# SCH-6-ESC4.net
KiCad netlist of a schematic drawn in Altium Designer
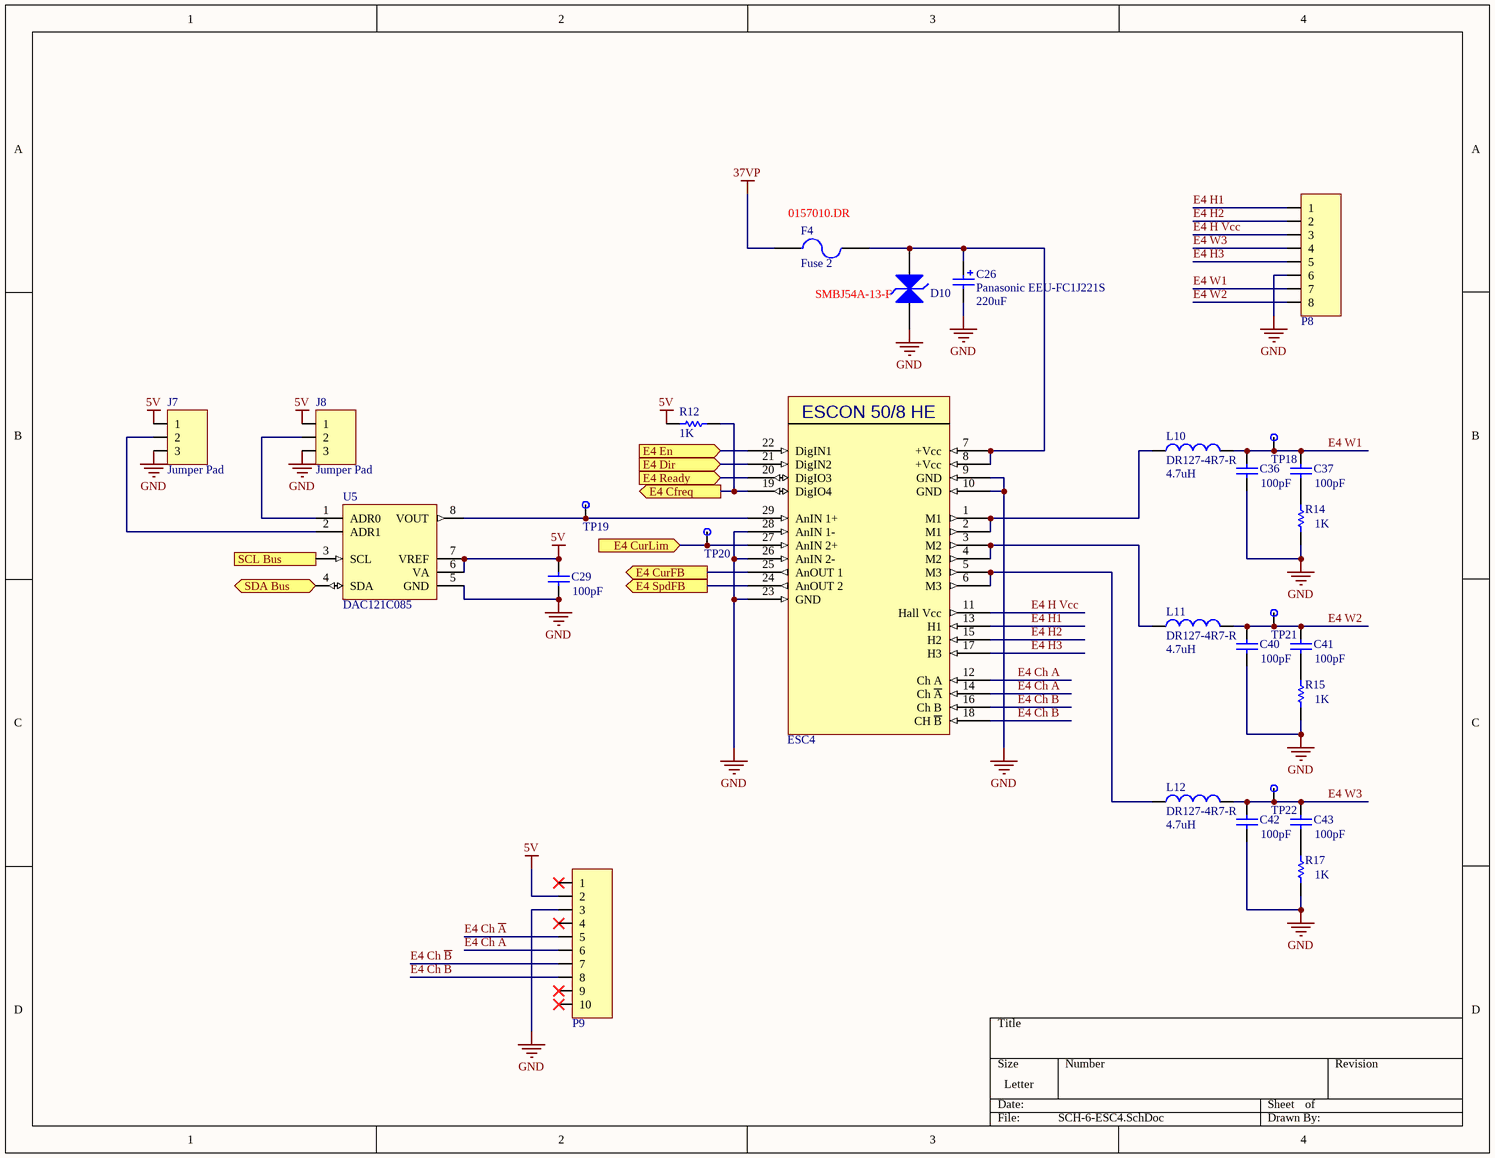
[diagram p0: SCH-6-ESC4.SchDoc]

(export (version "E")
  (design (tool "Eeschema 10.0.6"))
  (components
    (comp (ref "C26")
      (value "Panasonic EEU-FC1J221S")
      (footprint "Panasonic EEU-FC1J221S")
      (description "Polarized Capacitor (Radial)")
      (fields (field (name "ALTIUM_VALUE") "220uF"))
      (libsource (lib "RSX_Capacitors") (part "Panasonic EEU-FC1J221S"))
    )
    (comp (ref "C29")
      (value "100pF")
      (footprint "C1206")
      (description "Capacitor (Semiconductor SIM Model)")
      (fields (field (name "Comment") "Cap Semi") (field (name "PUBLISHER") "Altium Limited"))
      (libsource (lib "Miscellaneous Devices") (part "Cap Semi"))
    )
    (comp (ref "C36")
      (value "100pF")
      (footprint "C1206")
      (description "Capacitor (Semiconductor SIM Model)")
      (fields (field (name "Comment") "Cap Semi") (field (name "PUBLISHER") "Altium Limited"))
      (libsource (lib "Miscellaneous Devices") (part "Cap Semi"))
    )
    (comp (ref "C37")
      (value "100pF")
      (footprint "C1206")
      (description "Capacitor (Semiconductor SIM Model)")
      (fields (field (name "Comment") "Cap Semi") (field (name "PUBLISHER") "Altium Limited"))
      (libsource (lib "Miscellaneous Devices") (part "Cap Semi"))
    )
    (comp (ref "C40")
      (value "100pF")
      (footprint "C1206")
      (description "Capacitor (Semiconductor SIM Model)")
      (fields (field (name "Comment") "Cap Semi") (field (name "PUBLISHER") "Altium Limited"))
      (libsource (lib "Miscellaneous Devices") (part "Cap Semi"))
    )
    (comp (ref "C41")
      (value "100pF")
      (footprint "C1206")
      (description "Capacitor (Semiconductor SIM Model)")
      (fields (field (name "Comment") "Cap Semi") (field (name "PUBLISHER") "Altium Limited"))
      (libsource (lib "Miscellaneous Devices") (part "Cap Semi"))
    )
    (comp (ref "C42")
      (value "100pF")
      (footprint "C1206")
      (description "Capacitor (Semiconductor SIM Model)")
      (fields (field (name "Comment") "Cap Semi") (field (name "PUBLISHER") "Altium Limited"))
      (libsource (lib "Miscellaneous Devices") (part "Cap Semi"))
    )
    (comp (ref "C43")
      (value "100pF")
      (footprint "C1206")
      (description "Capacitor (Semiconductor SIM Model)")
      (fields (field (name "Comment") "Cap Semi") (field (name "PUBLISHER") "Altium Limited"))
      (libsource (lib "Miscellaneous Devices") (part "Cap Semi"))
    )
    (comp (ref "D10")
      (value "TVS_DIODE")
      (footprint "SMBJ54A-13-F")
      (description "TVS Diode")
      (fields (field (name "PUBLISHER") "Altium Limited"))
      (libsource (lib "RSX_Diodes") (part "TVS_DIODE"))
    )
    (comp (ref "ESC4")
      (value "ESCON 50/8 HE")
      (footprint "ESCON 50/8 HE")
      (description "ESCON Module 50/8 HE Servocontroller")
      (libsource (lib "RSX_Modules") (part "ESCON 50/8 HE"))
    )
    (comp (ref "F4")
      (value "Fuse 2")
      (footprint "0157010.DR")
      (description "Fuse")
      (fields (field (name "PUBLISHER") "Altium Limited"))
      (libsource (lib "RSX_Miscellaneous") (part "Fuse 2"))
    )
    (comp (ref "J7")
      (value "Jumper Pad")
      (footprint "3 Pad TH")
      (libsource (lib "RSX_Test_Points") (part "3 Pad Jump Sel"))
    )
    (comp (ref "J8")
      (value "Jumper Pad")
      (footprint "3 Pad TH")
      (libsource (lib "RSX_Test_Points") (part "3 Pad Jump Sel"))
    )
    (comp (ref "L10")
      (value "DR127-4R7-R")
      (footprint "DR127-4R7-R")
      (description "4.7µH Shielded Wirewound Inductor 8.25A 9.17mOhm Nonstandard")
      (fields (field (name "ALTIUM_VALUE") "4.7uH") (field (name "PUBLISHER") "Altium Limited"))
      (libsource (lib "RSX_Inductors") (part "DR127-4R7-R"))
    )
    (comp (ref "L11")
      (value "DR127-4R7-R")
      (footprint "DR127-4R7-R")
      (description "4.7µH Shielded Wirewound Inductor 8.25A 9.17mOhm Nonstandard")
      (fields (field (name "ALTIUM_VALUE") "4.7uH") (field (name "PUBLISHER") "Altium Limited"))
      (libsource (lib "RSX_Inductors") (part "DR127-4R7-R"))
    )
    (comp (ref "L12")
      (value "DR127-4R7-R")
      (footprint "DR127-4R7-R")
      (description "4.7µH Shielded Wirewound Inductor 8.25A 9.17mOhm Nonstandard")
      (fields (field (name "ALTIUM_VALUE") "4.7uH") (field (name "PUBLISHER") "Altium Limited"))
      (libsource (lib "RSX_Inductors") (part "DR127-4R7-R"))
    )
    (comp (ref "P8")
      (value "Mini-Fit Jr 8 Pos")
      (footprint "Molex Mini-Fit Jr 0039281083")
      (libsource (lib "RSX_Connectors") (part "Molex Mini-Fit Jr 8pos Vert"))
    )
    (comp (ref "P9")
      (value "Header_10_Pos_Ribbon Male")
      (footprint "3M_2510-6002UB")
      (description "3M_2510-6002UB")
      (libsource (lib "RSX_Connectors") (part "Header_10_Pos_Ribbon Male"))
    )
    (comp (ref "R12")
      (value "1K")
      (footprint "RESC1608X06N_0603")
      (description "Resistor")
      (fields (field (name "Comment") "Res1") (field (name "PUBLISHER") "Altium Limited"))
      (libsource (lib "RSX_Resistors") (part "Res1"))
    )
    (comp (ref "R14")
      (value "1K")
      (footprint "RESC1608X06N_0603")
      (description "Resistor")
      (fields (field (name "Comment") "Res1") (field (name "PUBLISHER") "Altium Limited"))
      (libsource (lib "RSX_Resistors") (part "Res1"))
    )
    (comp (ref "R15")
      (value "1K")
      (footprint "RESC1608X06N_0603")
      (description "Resistor")
      (fields (field (name "Comment") "Res1") (field (name "PUBLISHER") "Altium Limited"))
      (libsource (lib "RSX_Resistors") (part "Res1"))
    )
    (comp (ref "R17")
      (value "1K")
      (footprint "RESC1608X06N_0603")
      (description "Resistor")
      (fields (field (name "Comment") "Res1") (field (name "PUBLISHER") "Altium Limited"))
      (libsource (lib "RSX_Resistors") (part "Res1"))
    )
    (comp (ref "TP18")
      (value "TestPt")
      (footprint "50_MIL_PAD")
      (libsource (lib "RSX_Test_Points") (part "TestPt"))
    )
    (comp (ref "TP19")
      (value "TestPt")
      (footprint "50_MIL_PAD")
      (libsource (lib "RSX_Test_Points") (part "TestPt"))
    )
    (comp (ref "TP20")
      (value "TestPt")
      (footprint "50_MIL_PAD")
      (libsource (lib "RSX_Test_Points") (part "TestPt"))
    )
    (comp (ref "TP21")
      (value "TestPt")
      (footprint "50_MIL_PAD")
      (libsource (lib "RSX_Test_Points") (part "TestPt"))
    )
    (comp (ref "TP22")
      (value "TestPt")
      (footprint "50_MIL_PAD")
      (libsource (lib "RSX_Test_Points") (part "TestPt"))
    )
    (comp (ref "U5")
      (value "DAC121C085")
      (footprint "MUA08A_L")
      (fields (field (name "MANUFACTURER") "National Semiconductor"))
      (libsource (lib "RSX_Schematics") (part "DAC121C085"))
    )
  )
  (nets
    (net (code "1") (name "/E4 Cfreq") (class "Default")
      (node (ref "ESC4") (pin "19") (pinfunction "DigIO4_19") (pintype "bidirectional"))
      (node (ref "R12") (pin "1") (pinfunction "1_1") (pintype "passive"))
    )
    (net (code "2") (name "/E4 Ch A") (class "Default")
      (node (ref "ESC4") (pin "12") (pinfunction "Ch_A_12") (pintype "input"))
      (node (ref "P9") (pin "6") (pinfunction "6_6") (pintype "passive"))
    )
    (net (code "3") (name "/E4 Ch B") (class "Default")
      (node (ref "ESC4") (pin "16") (pinfunction "Ch_B_16") (pintype "input"))
      (node (ref "P9") (pin "8") (pinfunction "8_8") (pintype "passive"))
    )
    (net (code "4") (name "/E4 Ch ~{A}") (class "Default")
      (node (ref "ESC4") (pin "14") (pinfunction "Ch_~{A}_14") (pintype "input"))
      (node (ref "P9") (pin "5") (pinfunction "5_5") (pintype "passive"))
    )
    (net (code "5") (name "/E4 Ch ~{B}") (class "Default")
      (node (ref "ESC4") (pin "18") (pinfunction "CH_~{B}_18") (pintype "input"))
      (node (ref "P9") (pin "7") (pinfunction "7_7") (pintype "passive"))
    )
    (net (code "6") (name "/E4 CurFB") (class "Default")
      (node (ref "ESC4") (pin "25") (pinfunction "AnOUT_1_25") (pintype "output"))
    )
    (net (code "7") (name "/E4 CurLim") (class "Default")
      (node (ref "ESC4") (pin "27") (pinfunction "AnIN_2+_27") (pintype "input"))
      (node (ref "TP20") (pin "1") (pinfunction "1_1") (pintype "passive"))
    )
    (net (code "8") (name "/E4 Dir") (class "Default")
      (node (ref "ESC4") (pin "21") (pinfunction "DigIN2_21") (pintype "input"))
    )
    (net (code "9") (name "/E4 En") (class "Default")
      (node (ref "ESC4") (pin "22") (pinfunction "DigIN1_22") (pintype "input"))
    )
    (net (code "10") (name "/E4 H Vcc") (class "Default")
      (node (ref "ESC4") (pin "11") (pinfunction "Hall_Vcc_11") (pintype "output"))
      (node (ref "P8") (pin "3") (pinfunction "3_3") (pintype "passive"))
    )
    (net (code "11") (name "/E4 H1") (class "Default")
      (node (ref "ESC4") (pin "13") (pinfunction "H1_13") (pintype "input"))
      (node (ref "P8") (pin "1") (pinfunction "1_1") (pintype "passive"))
    )
    (net (code "12") (name "/E4 H2") (class "Default")
      (node (ref "ESC4") (pin "15") (pinfunction "H2_15") (pintype "input"))
      (node (ref "P8") (pin "2") (pinfunction "2_2") (pintype "passive"))
    )
    (net (code "13") (name "/E4 H3") (class "Default")
      (node (ref "ESC4") (pin "17") (pinfunction "H3_17") (pintype "input"))
      (node (ref "P8") (pin "5") (pinfunction "5_5") (pintype "passive"))
    )
    (net (code "14") (name "/E4 Ready") (class "Default")
      (node (ref "ESC4") (pin "20") (pinfunction "DigIO3_20") (pintype "bidirectional"))
    )
    (net (code "15") (name "/E4 SpdFB") (class "Default")
      (node (ref "ESC4") (pin "24") (pinfunction "AnOUT_2_24") (pintype "output"))
    )
    (net (code "16") (name "/E4 W1") (class "Default")
      (node (ref "C36") (pin "2") (pinfunction "2_2") (pintype "passive"))
      (node (ref "C37") (pin "2") (pinfunction "2_2") (pintype "passive"))
      (node (ref "L10") (pin "2") (pinfunction "2_2") (pintype "passive"))
      (node (ref "P8") (pin "7") (pinfunction "7_7") (pintype "passive"))
      (node (ref "TP18") (pin "1") (pinfunction "1_1") (pintype "passive"))
    )
    (net (code "17") (name "/E4 W2") (class "Default")
      (node (ref "C40") (pin "2") (pinfunction "2_2") (pintype "passive"))
      (node (ref "C41") (pin "2") (pinfunction "2_2") (pintype "passive"))
      (node (ref "L11") (pin "2") (pinfunction "2_2") (pintype "passive"))
      (node (ref "P8") (pin "8") (pinfunction "8_8") (pintype "passive"))
      (node (ref "TP21") (pin "1") (pinfunction "1_1") (pintype "passive"))
    )
    (net (code "18") (name "/E4 W3") (class "Default")
      (node (ref "C42") (pin "2") (pinfunction "2_2") (pintype "passive"))
      (node (ref "C43") (pin "2") (pinfunction "2_2") (pintype "passive"))
      (node (ref "L12") (pin "2") (pinfunction "2_2") (pintype "passive"))
      (node (ref "P8") (pin "4") (pinfunction "4_4") (pintype "passive"))
      (node (ref "TP22") (pin "1") (pinfunction "1_1") (pintype "passive"))
    )
    (net (code "19") (name "/SCL Bus") (class "Default")
      (node (ref "U5") (pin "3") (pinfunction "SCL_3") (pintype "input"))
    )
    (net (code "20") (name "/SDA Bus") (class "Default")
      (node (ref "U5") (pin "4") (pinfunction "SDA_4") (pintype "bidirectional"))
    )
    (net (code "21") (name "5V") (class "Default")
      (node (ref "C29") (pin "2") (pinfunction "2_2") (pintype "passive"))
      (node (ref "J7") (pin "1") (pinfunction "1_1") (pintype "passive"))
      (node (ref "J8") (pin "1") (pinfunction "1_1") (pintype "passive"))
      (node (ref "P9") (pin "2") (pinfunction "2_2") (pintype "passive"))
      (node (ref "R12") (pin "2") (pinfunction "2_2") (pintype "passive"))
      (node (ref "U5") (pin "6") (pinfunction "VA_6") (pintype "power_in"))
      (node (ref "U5") (pin "7") (pinfunction "VREF_7") (pintype "power_in"))
    )
    (net (code "22") (name "37VP") (class "Default")
      (node (ref "F4") (pin "1") (pinfunction "1_1") (pintype "passive"))
    )
    (net (code "23") (name "GND") (class "Default")
      (node (ref "C26") (pin "2") (pinfunction "2_2") (pintype "passive"))
      (node (ref "C29") (pin "1") (pinfunction "1_1") (pintype "passive"))
      (node (ref "C36") (pin "1") (pinfunction "1_1") (pintype "passive"))
      (node (ref "C40") (pin "1") (pinfunction "1_1") (pintype "passive"))
      (node (ref "C42") (pin "1") (pinfunction "1_1") (pintype "passive"))
      (node (ref "D10") (pin "1") (pinfunction "A_1") (pintype "passive"))
      (node (ref "ESC4") (pin "10") (pinfunction "GND_10") (pintype "input"))
      (node (ref "ESC4") (pin "23") (pinfunction "GND_23") (pintype "input"))
      (node (ref "ESC4") (pin "26") (pinfunction "AnIN_2-_26") (pintype "input"))
      (node (ref "ESC4") (pin "28") (pinfunction "AnIN_1-_28") (pintype "input"))
      (node (ref "ESC4") (pin "9") (pinfunction "GND_9") (pintype "input"))
      (node (ref "J7") (pin "3") (pinfunction "3_3") (pintype "passive"))
      (node (ref "J8") (pin "3") (pinfunction "3_3") (pintype "passive"))
      (node (ref "P8") (pin "6") (pinfunction "6_6") (pintype "passive"))
      (node (ref "P9") (pin "3") (pinfunction "3_3") (pintype "passive"))
      (node (ref "R14") (pin "1") (pinfunction "1_1") (pintype "passive"))
      (node (ref "R15") (pin "1") (pinfunction "1_1") (pintype "passive"))
      (node (ref "R17") (pin "1") (pinfunction "1_1") (pintype "passive"))
      (node (ref "U5") (pin "5") (pinfunction "GND_5") (pintype "power_in"))
    )
    (net (code "24") (name "Net-(C37-Pad1)") (class "Default")
      (node (ref "C37") (pin "1") (pinfunction "1_1") (pintype "passive"))
      (node (ref "R14") (pin "2") (pinfunction "2_2") (pintype "passive"))
    )
    (net (code "25") (name "Net-(C41-Pad1)") (class "Default")
      (node (ref "C41") (pin "1") (pinfunction "1_1") (pintype "passive"))
      (node (ref "R15") (pin "2") (pinfunction "2_2") (pintype "passive"))
    )
    (net (code "26") (name "Net-(C43-Pad1)") (class "Default")
      (node (ref "C43") (pin "1") (pinfunction "1_1") (pintype "passive"))
      (node (ref "R17") (pin "2") (pinfunction "2_2") (pintype "passive"))
    )
    (net (code "27") (name "Net-(D10-K)") (class "Default")
      (node (ref "C26") (pin "1") (pinfunction "1_1") (pintype "passive"))
      (node (ref "D10") (pin "2") (pinfunction "K_2") (pintype "passive"))
      (node (ref "ESC4") (pin "7") (pinfunction "+Vcc_7") (pintype "input"))
      (node (ref "ESC4") (pin "8") (pinfunction "+Vcc_8") (pintype "input"))
      (node (ref "F4") (pin "2") (pinfunction "2_2") (pintype "passive"))
    )
    (net (code "28") (name "Net-(ESC4-AnIN_1+)") (class "Default")
      (node (ref "ESC4") (pin "29") (pinfunction "AnIN_1+_29") (pintype "input"))
      (node (ref "TP19") (pin "1") (pinfunction "1_1") (pintype "passive"))
      (node (ref "U5") (pin "8") (pinfunction "VOUT_8") (pintype "output"))
    )
    (net (code "29") (name "Net-(ESC4-M1-Pad1)") (class "Default")
      (node (ref "ESC4") (pin "1") (pinfunction "M1_1") (pintype "output"))
      (node (ref "ESC4") (pin "2") (pinfunction "M1_2") (pintype "output"))
      (node (ref "L10") (pin "1") (pinfunction "1_1") (pintype "passive"))
    )
    (net (code "30") (name "Net-(ESC4-M2-Pad3)") (class "Default")
      (node (ref "ESC4") (pin "3") (pinfunction "M2_3") (pintype "output"))
      (node (ref "ESC4") (pin "4") (pinfunction "M2_4") (pintype "output"))
      (node (ref "L11") (pin "1") (pinfunction "1_1") (pintype "passive"))
    )
    (net (code "31") (name "Net-(ESC4-M3-Pad5)") (class "Default")
      (node (ref "ESC4") (pin "5") (pinfunction "M3_5") (pintype "output"))
      (node (ref "ESC4") (pin "6") (pinfunction "M3_6") (pintype "output"))
      (node (ref "L12") (pin "1") (pinfunction "1_1") (pintype "passive"))
    )
    (net (code "32") (name "Net-(U5-ADR0)") (class "Default")
      (node (ref "J8") (pin "2") (pinfunction "2_2") (pintype "passive"))
      (node (ref "U5") (pin "1") (pinfunction "ADR0_1") (pintype "tri_state"))
    )
    (net (code "33") (name "Net-(U5-ADR1)") (class "Default")
      (node (ref "J7") (pin "2") (pinfunction "2_2") (pintype "passive"))
      (node (ref "U5") (pin "2") (pinfunction "ADR1_2") (pintype "tri_state"))
    )
    (net (code "34") (name "unconnected-(P9-Pad1)") (class "Default")
      (node (ref "P9") (pin "1") (pinfunction "1_1") (pintype "passive+no_connect"))
    )
    (net (code "35") (name "unconnected-(P9-Pad4)") (class "Default")
      (node (ref "P9") (pin "4") (pinfunction "4_4") (pintype "passive+no_connect"))
    )
    (net (code "36") (name "unconnected-(P9-Pad9)") (class "Default")
      (node (ref "P9") (pin "9") (pinfunction "9_9") (pintype "passive+no_connect"))
    )
    (net (code "37") (name "unconnected-(P9-Pad10)") (class "Default")
      (node (ref "P9") (pin "10") (pinfunction "10_10") (pintype "passive+no_connect"))
    )
  )
)
